# HB-OU-MP3-LED_V1_3.net
KiCad netlist of a schematic drawn in EAGLE
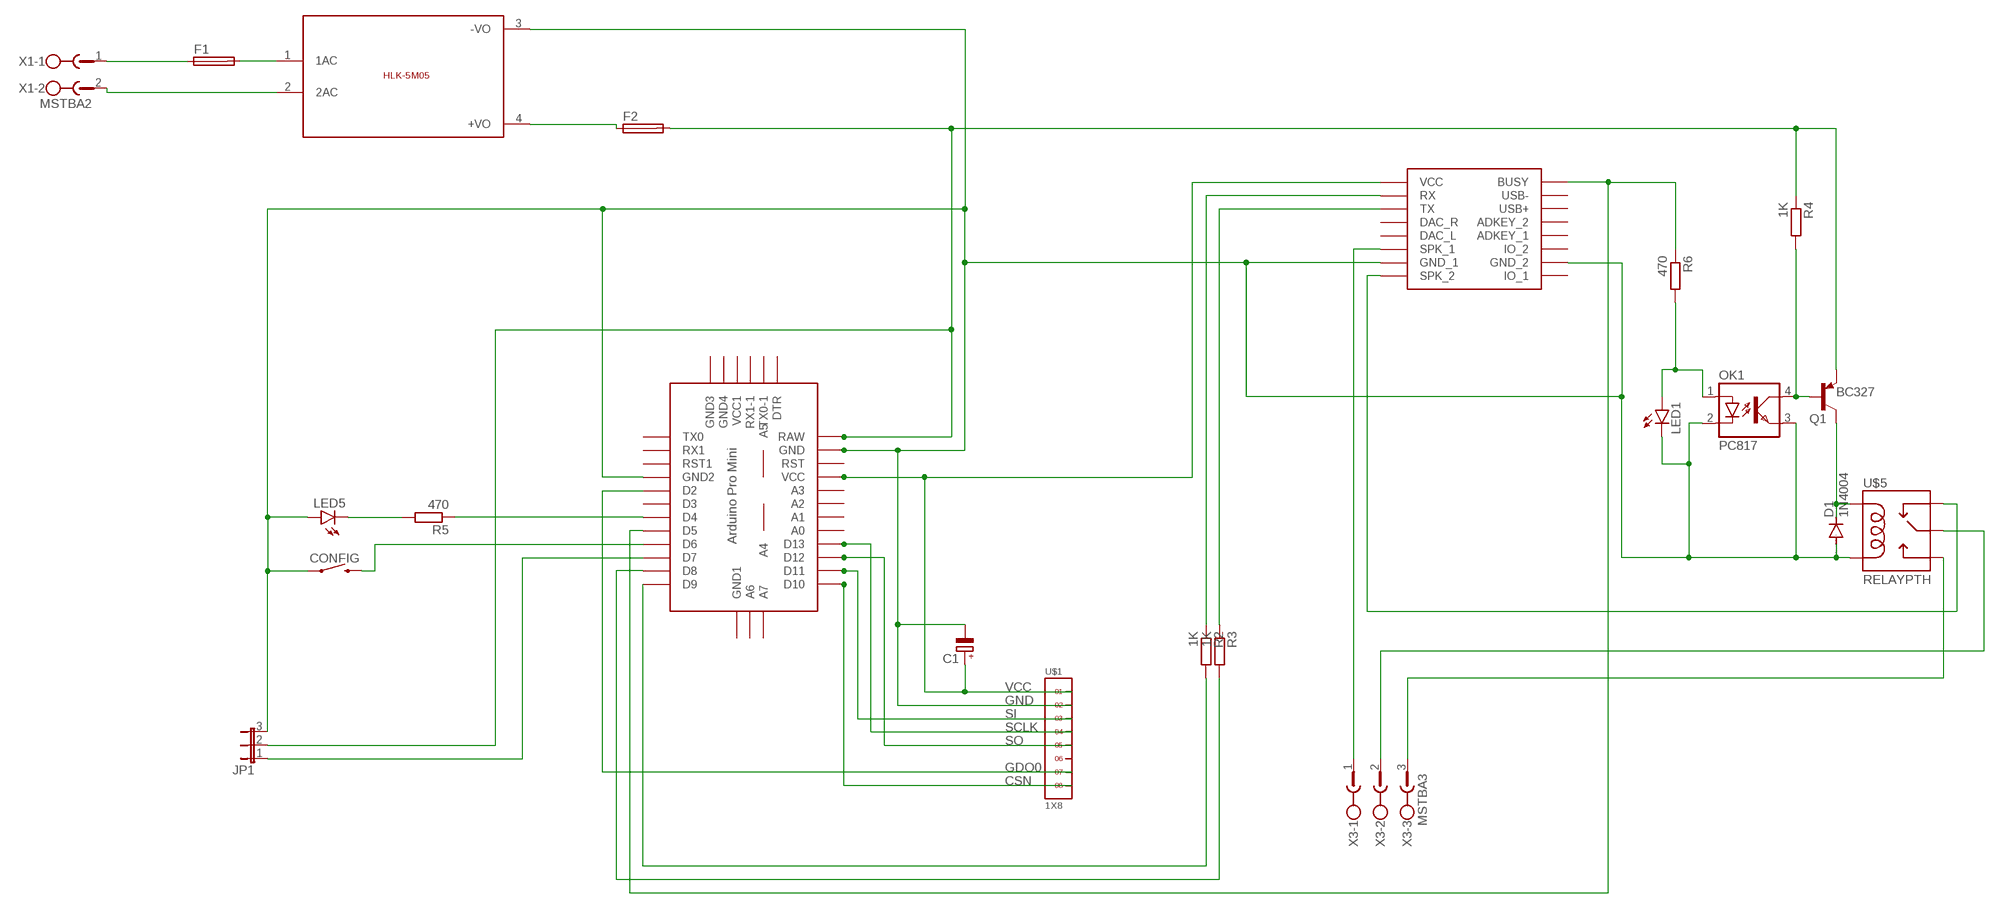
[diagram p0: schematic, sheet 1]

(export (version "E")
  (design (tool "Eeschema 10.0.6"))
  (components
    (comp (ref "C1")
      (value "CPOL-EUE2.5-5")
      (footprint "eagle-import:E2,5-5")
      (libsource (lib "eagle-import") (part "CPOL-EUE2.5-5"))
    )
    (comp (ref "CONFIG")
      (value "MOMENTARY-SWITCH-SPST-PTH-6.0MM-KIT")
      (footprint "eagle-import:TACTILE_SWITCH_PTH_6.0MM_KIT")
      (libsource (lib "eagle-import") (part "MOMENTARY-SWITCH-SPST-PTH-6.0MM-KIT"))
    )
    (comp (ref "D1")
      (value "1N4004")
      (footprint "eagle-import:DO41-10")
      (libsource (lib "eagle-import") (part "1N4004"))
    )
    (comp (ref "F1")
      (value "SH22,5A")
      (footprint "eagle-import:SH22,5A")
      (fields (field (name "MPN") "0031.7701.11"))
      (libsource (lib "eagle-import") (part "SH22,5A"))
    )
    (comp (ref "F2")
      (value "SH22,5A")
      (footprint "eagle-import:SH22,5A")
      (fields (field (name "MPN") "0031.7701.11"))
      (libsource (lib "eagle-import") (part "SH22,5A"))
    )
    (comp (ref "JP1")
      (value "JP2E")
      (footprint "eagle-import:JP2")
      (libsource (lib "eagle-import") (part "JP2E"))
    )
    (comp (ref "LED1")
      (value "LED3MM")
      (footprint "eagle-import:LED3MM")
      (libsource (lib "eagle-import") (part "LED3MM"))
    )
    (comp (ref "LED5")
      (value "LED3MM")
      (footprint "eagle-import:LED3MM")
      (libsource (lib "eagle-import") (part "LED3MM"))
    )
    (comp (ref "OK1")
      (value "PC817")
      (footprint "eagle-import:DIL04")
      (fields (field (name "MPN") "PC817X4J000F"))
      (libsource (lib "eagle-import") (part "PC817"))
    )
    (comp (ref "Q1")
      (value "BC327")
      (footprint "eagle-import:TO92")
      (libsource (lib "eagle-import") (part "BC327"))
    )
    (comp (ref "R2")
      (value "1K")
      (footprint "eagle-import:0309_10")
      (libsource (lib "eagle-import") (part "R-EU_0309/10"))
    )
    (comp (ref "R3")
      (value "1K")
      (footprint "eagle-import:0309_10")
      (libsource (lib "eagle-import") (part "R-EU_0309/10"))
    )
    (comp (ref "R4")
      (value "1K")
      (footprint "eagle-import:0309_10")
      (libsource (lib "eagle-import") (part "R-EU_0309/10"))
    )
    (comp (ref "R5")
      (value "470")
      (footprint "eagle-import:0309_10")
      (libsource (lib "eagle-import") (part "R-EU_0309/10"))
    )
    (comp (ref "R6")
      (value "470")
      (footprint "eagle-import:0309_10")
      (libsource (lib "eagle-import") (part "R-EU_0309/10"))
    )
    (comp (ref "U$1")
      (value "1X8")
      (footprint "eagle-import:1X8")
      (libsource (lib "eagle-import") (part "1X8"))
    )
    (comp (ref "U$2")
      (value "ABK-PRO-MINI")
      (footprint "eagle-import:ABK-PRO-MINI")
      (libsource (lib "eagle-import") (part "ABK-PRO-MINI"))
    )
    (comp (ref "U$3")
      (value "5VDC/5W")
      (footprint "eagle-import:HLK-5M05")
      (libsource (lib "eagle-import") (part "HLK-5M05"))
    )
    (comp (ref "U$4")
      (value "DFPLAYER")
      (footprint "eagle-import:DFPLAYER")
      (libsource (lib "eagle-import") (part "DFPLAYER"))
    )
    (comp (ref "U$5")
      (value "RELAYPTH")
      (footprint "eagle-import:SRD-05VDC-SL-C")
      (libsource (lib "eagle-import") (part "RELAYPTH"))
    )
    (comp (ref "X1")
      (value "MSTBA2")
      (footprint "eagle-import:MSTBA2")
      (fields (field (name "MF") "FARNELL") (field (name "MPN") "1757242"))
      (libsource (lib "eagle-import") (part "MSTBA2"))
    )
    (comp (ref "X3")
      (value "MSTBA3")
      (footprint "eagle-import:MSTBA3")
      (fields (field (name "MF") "FARNELL") (field (name "MPN") "1757255"))
      (libsource (lib "eagle-import") (part "MSTBA3"))
    )
  )
  (nets
    (net (code "1") (name "/CSN") (class "Default")
      (node (ref "U$1") (pin "8") (pinfunction "8_8") (pintype "bidirectional"))
      (node (ref "U$2") (pin "D10") (pinfunction "D10_D10") (pintype "bidirectional"))
    )
    (net (code "2") (name "/GDO0") (class "Default")
      (node (ref "U$1") (pin "7") (pinfunction "7_7") (pintype "bidirectional"))
      (node (ref "U$2") (pin "D2") (pinfunction "D2_D2") (pintype "bidirectional"))
    )
    (net (code "3") (name "/GND") (class "Default")
      (node (ref "C1") (pin "-") (pinfunction "-_-") (pintype "passive"))
      (node (ref "CONFIG") (pin "1") (pinfunction "1_1") (pintype "passive"))
      (node (ref "D1") (pin "A") (pinfunction "A_A") (pintype "passive"))
      (node (ref "JP1") (pin "3") (pinfunction "3_3") (pintype "passive"))
      (node (ref "LED1") (pin "K") (pinfunction "C_K") (pintype "passive"))
      (node (ref "LED5") (pin "A") (pinfunction "A_A") (pintype "passive"))
      (node (ref "OK1") (pin "2") (pinfunction "C_2") (pintype "passive"))
      (node (ref "OK1") (pin "3") (pinfunction "EMIT_3") (pintype "passive"))
      (node (ref "U$1") (pin "2") (pinfunction "2_2") (pintype "bidirectional"))
      (node (ref "U$2") (pin "GND") (pinfunction "GND_GND") (pintype "bidirectional"))
      (node (ref "U$2") (pin "GND1") (pinfunction "GND2_GND1") (pintype "bidirectional"))
      (node (ref "U$3") (pin "3") (pinfunction "-VO_3") (pintype "bidirectional"))
      (node (ref "U$4") (pin "GND_1") (pinfunction "GND_1_GND_1") (pintype "bidirectional"))
      (node (ref "U$4") (pin "GND_2") (pinfunction "GND_2_GND_2") (pintype "bidirectional"))
      (node (ref "U$5") (pin "COIL0") (pinfunction "COIL0_COIL0") (pintype "bidirectional"))
    )
    (net (code "4") (name "/SCLK") (class "Default")
      (node (ref "U$1") (pin "4") (pinfunction "4_4") (pintype "bidirectional"))
      (node (ref "U$2") (pin "D13") (pinfunction "D13_D13") (pintype "bidirectional"))
    )
    (net (code "5") (name "/SI") (class "Default")
      (node (ref "U$1") (pin "3") (pinfunction "3_3") (pintype "bidirectional"))
      (node (ref "U$2") (pin "D11") (pinfunction "D11_D11") (pintype "bidirectional"))
    )
    (net (code "6") (name "/SO") (class "Default")
      (node (ref "U$1") (pin "5") (pinfunction "5_5") (pintype "bidirectional"))
      (node (ref "U$2") (pin "D12") (pinfunction "D12_D12") (pintype "bidirectional"))
    )
    (net (code "7") (name "/VCC") (class "Default")
      (node (ref "C1") (pin "+") (pinfunction "+_+") (pintype "passive"))
      (node (ref "U$1") (pin "1") (pinfunction "1_1") (pintype "bidirectional"))
      (node (ref "U$2") (pin "VCC") (pinfunction "VCC_VCC") (pintype "bidirectional"))
      (node (ref "U$4") (pin "VCC") (pinfunction "VCC_VCC") (pintype "bidirectional"))
    )
    (net (code "8") (name "Net-(CONFIG-2)") (class "Default")
      (node (ref "CONFIG") (pin "3") (pinfunction "2_3") (pintype "passive"))
      (node (ref "U$2") (pin "D6") (pinfunction "D6_D6") (pintype "bidirectional"))
    )
    (net (code "9") (name "Net-(F1-Pad1)") (class "Default")
      (node (ref "F1") (pin "1") (pinfunction "1_1") (pintype "passive"))
      (node (ref "X1") (pin "1") (pinfunction "1_1") (pintype "passive"))
    )
    (net (code "10") (name "Net-(JP1-Pad1)") (class "Default")
      (node (ref "JP1") (pin "1") (pinfunction "1_1") (pintype "passive"))
      (node (ref "U$2") (pin "D7") (pinfunction "D7_D7") (pintype "bidirectional"))
    )
    (net (code "11") (name "Net-(LED5-C)") (class "Default")
      (node (ref "LED5") (pin "K") (pinfunction "C_K") (pintype "passive"))
      (node (ref "R5") (pin "2") (pinfunction "2_2") (pintype "passive"))
    )
    (net (code "12") (name "Net-(OK1-A)") (class "Default")
      (node (ref "LED1") (pin "A") (pinfunction "A_A") (pintype "passive"))
      (node (ref "OK1") (pin "1") (pinfunction "A_1") (pintype "passive"))
      (node (ref "R6") (pin "2") (pinfunction "2_2") (pintype "passive"))
    )
    (net (code "13") (name "Net-(OK1-COL)") (class "Default")
      (node (ref "OK1") (pin "4") (pinfunction "COL_4") (pintype "passive"))
      (node (ref "Q1") (pin "2") (pinfunction "B_2") (pintype "passive"))
      (node (ref "R4") (pin "2") (pinfunction "2_2") (pintype "passive"))
    )
    (net (code "14") (name "Net-(Q1-C)") (class "Default")
      (node (ref "D1") (pin "C") (pinfunction "C_C") (pintype "passive"))
      (node (ref "Q1") (pin "3") (pinfunction "C_3") (pintype "passive"))
      (node (ref "U$5") (pin "COIL1") (pinfunction "COIL1_COIL1") (pintype "bidirectional"))
    )
    (net (code "15") (name "Net-(Q1-E)") (class "Default")
      (node (ref "F2") (pin "2") (pinfunction "2_2") (pintype "passive"))
      (node (ref "JP1") (pin "2") (pinfunction "2_2") (pintype "passive"))
      (node (ref "Q1") (pin "1") (pinfunction "E_1") (pintype "passive"))
      (node (ref "R4") (pin "1") (pinfunction "1_1") (pintype "passive"))
      (node (ref "U$2") (pin "RAW") (pinfunction "RAW_RAW") (pintype "bidirectional"))
    )
    (net (code "16") (name "Net-(R2-Pad1)") (class "Default")
      (node (ref "R2") (pin "1") (pinfunction "1_1") (pintype "passive"))
      (node (ref "U$4") (pin "RX") (pinfunction "RX_RX") (pintype "bidirectional"))
    )
    (net (code "17") (name "Net-(R2-Pad2)") (class "Default")
      (node (ref "R2") (pin "2") (pinfunction "2_2") (pintype "passive"))
      (node (ref "U$2") (pin "D9") (pinfunction "D9_D9") (pintype "bidirectional"))
    )
    (net (code "18") (name "Net-(R3-Pad1)") (class "Default")
      (node (ref "R3") (pin "1") (pinfunction "1_1") (pintype "passive"))
      (node (ref "U$4") (pin "TX") (pinfunction "TX_TX") (pintype "bidirectional"))
    )
    (net (code "19") (name "Net-(R3-Pad2)") (class "Default")
      (node (ref "R3") (pin "2") (pinfunction "2_2") (pintype "passive"))
      (node (ref "U$2") (pin "D8") (pinfunction "D8_D8") (pintype "bidirectional"))
    )
    (net (code "20") (name "Net-(R5-Pad1)") (class "Default")
      (node (ref "R5") (pin "1") (pinfunction "1_1") (pintype "passive"))
      (node (ref "U$2") (pin "D4") (pinfunction "D4_D4") (pintype "bidirectional"))
    )
    (net (code "21") (name "Net-(R6-Pad1)") (class "Default")
      (node (ref "R6") (pin "1") (pinfunction "1_1") (pintype "passive"))
      (node (ref "U$2") (pin "D5") (pinfunction "D5_D5") (pintype "bidirectional"))
      (node (ref "U$4") (pin "BUSY") (pinfunction "BUSY_BUSY") (pintype "bidirectional"))
    )
    (net (code "22") (name "Net-(U$3-+VO)") (class "Default")
      (node (ref "F2") (pin "1") (pinfunction "1_1") (pintype "passive"))
      (node (ref "U$3") (pin "4") (pinfunction "+VO_4") (pintype "bidirectional"))
    )
    (net (code "23") (name "Net-(U$3-1AC)") (class "Default")
      (node (ref "F1") (pin "2") (pinfunction "2_2") (pintype "passive"))
      (node (ref "U$3") (pin "1") (pinfunction "1AC_1") (pintype "bidirectional"))
    )
    (net (code "24") (name "Net-(U$3-2AC)") (class "Default")
      (node (ref "U$3") (pin "2") (pinfunction "2AC_2") (pintype "bidirectional"))
      (node (ref "X1") (pin "2") (pinfunction "1_2") (pintype "passive"))
    )
    (net (code "25") (name "Net-(U$4-SPK_1)") (class "Default")
      (node (ref "U$4") (pin "SPK1") (pinfunction "SPK_1_SPK1") (pintype "bidirectional"))
      (node (ref "X3") (pin "1") (pinfunction "1_1") (pintype "passive"))
    )
    (net (code "26") (name "Net-(U$4-SPK_2)") (class "Default")
      (node (ref "U$4") (pin "SPK2") (pinfunction "SPK_2_SPK2") (pintype "bidirectional"))
      (node (ref "U$5") (pin "SWCLOSED") (pinfunction "SWCLOSE_SWCLOSED") (pintype "bidirectional"))
    )
    (net (code "27") (name "Net-(X3B-1)") (class "Default")
      (node (ref "U$5") (pin "SWCOMMON") (pinfunction "SWCOMMON_SWCOMMON") (pintype "bidirectional"))
      (node (ref "X3") (pin "2") (pinfunction "1_2") (pintype "passive"))
    )
    (net (code "28") (name "Net-(X3C-1)") (class "Default")
      (node (ref "U$5") (pin "SWOPEN") (pinfunction "SWOPEN_SWOPEN") (pintype "bidirectional"))
      (node (ref "X3") (pin "3") (pinfunction "1_3") (pintype "passive"))
    )
    (net (code "29") (name "unconnected-(U$1-Pad6)") (class "Default")
      (node (ref "U$1") (pin "6") (pinfunction "6_6") (pintype "bidirectional"))
    )
    (net (code "30") (name "unconnected-(U$2-GND1-PadGND4)") (class "Default")
      (node (ref "U$2") (pin "GND4") (pinfunction "GND1_GND4") (pintype "bidirectional"))
    )
    (net (code "31") (name "unconnected-(U$2-GND3-PadGND2)") (class "Default")
      (node (ref "U$2") (pin "GND2") (pinfunction "GND3_GND2") (pintype "bidirectional"))
    )
    (net (code "32") (name "unconnected-(U$2-GND4-PadGND3)") (class "Default")
      (node (ref "U$2") (pin "GND3") (pinfunction "GND4_GND3") (pintype "bidirectional"))
    )
    (net (code "33") (name "unconnected-(U$2-PadA0)") (class "Default")
      (node (ref "U$2") (pin "A0") (pinfunction "A0_A0") (pintype "bidirectional"))
    )
    (net (code "34") (name "unconnected-(U$2-PadA1)") (class "Default")
      (node (ref "U$2") (pin "A1") (pinfunction "A1_A1") (pintype "bidirectional"))
    )
    (net (code "35") (name "unconnected-(U$2-PadA2)") (class "Default")
      (node (ref "U$2") (pin "A2") (pinfunction "A2_A2") (pintype "bidirectional"))
    )
    (net (code "36") (name "unconnected-(U$2-PadA3)") (class "Default")
      (node (ref "U$2") (pin "A3") (pinfunction "A3_A3") (pintype "bidirectional"))
    )
    (net (code "37") (name "unconnected-(U$2-PadA4)") (class "Default")
      (node (ref "U$2") (pin "A4") (pinfunction "A4_A4") (pintype "bidirectional"))
    )
    (net (code "38") (name "unconnected-(U$2-PadA5)") (class "Default")
      (node (ref "U$2") (pin "A5") (pinfunction "A5_A5") (pintype "bidirectional"))
    )
    (net (code "39") (name "unconnected-(U$2-PadA6)") (class "Default")
      (node (ref "U$2") (pin "A6") (pinfunction "A6_A6") (pintype "bidirectional"))
    )
    (net (code "40") (name "unconnected-(U$2-PadA7)") (class "Default")
      (node (ref "U$2") (pin "A7") (pinfunction "A7_A7") (pintype "bidirectional"))
    )
    (net (code "41") (name "unconnected-(U$2-PadD3)") (class "Default")
      (node (ref "U$2") (pin "D3") (pinfunction "D3_D3") (pintype "bidirectional"))
    )
    (net (code "42") (name "unconnected-(U$2-PadDTR)") (class "Default")
      (node (ref "U$2") (pin "DTR") (pinfunction "DTR_DTR") (pintype "bidirectional"))
    )
    (net (code "43") (name "unconnected-(U$2-PadRST)") (class "Default")
      (node (ref "U$2") (pin "RST") (pinfunction "RST_RST") (pintype "bidirectional"))
    )
    (net (code "44") (name "unconnected-(U$2-PadRST1)") (class "Default")
      (node (ref "U$2") (pin "RST1") (pinfunction "RST1_RST1") (pintype "bidirectional"))
    )
    (net (code "45") (name "unconnected-(U$2-PadRX1)") (class "Default")
      (node (ref "U$2") (pin "RX1") (pinfunction "RX1_RX1") (pintype "bidirectional"))
    )
    (net (code "46") (name "unconnected-(U$2-PadRX1-1)") (class "Default")
      (node (ref "U$2") (pin "RX1-1") (pinfunction "RX1-1_RX1-1") (pintype "bidirectional"))
    )
    (net (code "47") (name "unconnected-(U$2-PadTX0)") (class "Default")
      (node (ref "U$2") (pin "TX0") (pinfunction "TX0_TX0") (pintype "bidirectional"))
    )
    (net (code "48") (name "unconnected-(U$2-PadTX0-1)") (class "Default")
      (node (ref "U$2") (pin "TX0-1") (pinfunction "TX0-1_TX0-1") (pintype "bidirectional"))
    )
    (net (code "49") (name "unconnected-(U$2-PadVCC1)") (class "Default")
      (node (ref "U$2") (pin "VCC1") (pinfunction "VCC1_VCC1") (pintype "bidirectional"))
    )
    (net (code "50") (name "unconnected-(U$4-ADKEY_1-PadADKEY1)") (class "Default")
      (node (ref "U$4") (pin "ADKEY1") (pinfunction "ADKEY_1_ADKEY1") (pintype "bidirectional"))
    )
    (net (code "51") (name "unconnected-(U$4-ADKEY_2-PadADKEY2)") (class "Default")
      (node (ref "U$4") (pin "ADKEY2") (pinfunction "ADKEY_2_ADKEY2") (pintype "bidirectional"))
    )
    (net (code "52") (name "unconnected-(U$4-IO_1-PadIO1)") (class "Default")
      (node (ref "U$4") (pin "IO1") (pinfunction "IO_1_IO1") (pintype "bidirectional"))
    )
    (net (code "53") (name "unconnected-(U$4-IO_2-PadIO2)") (class "Default")
      (node (ref "U$4") (pin "IO2") (pinfunction "IO_2_IO2") (pintype "bidirectional"))
    )
    (net (code "54") (name "unconnected-(U$4-PadDAC_L)") (class "Default")
      (node (ref "U$4") (pin "DAC_L") (pinfunction "DAC_L_DAC_L") (pintype "bidirectional"))
    )
    (net (code "55") (name "unconnected-(U$4-PadDAC_R)") (class "Default")
      (node (ref "U$4") (pin "DAC_R") (pinfunction "DAC_R_DAC_R") (pintype "bidirectional"))
    )
    (net (code "56") (name "unconnected-(U$4-PadUSB+)") (class "Default")
      (node (ref "U$4") (pin "USB+") (pinfunction "USB+_USB+") (pintype "bidirectional"))
    )
    (net (code "57") (name "unconnected-(U$4-PadUSB-)") (class "Default")
      (node (ref "U$4") (pin "USB-") (pinfunction "USB-_USB-") (pintype "bidirectional"))
    )
  )
)
